# ecg_leaddetection_module_v2_0_1_jan2024.net
KiCad netlist of a schematic drawn in EAGLE
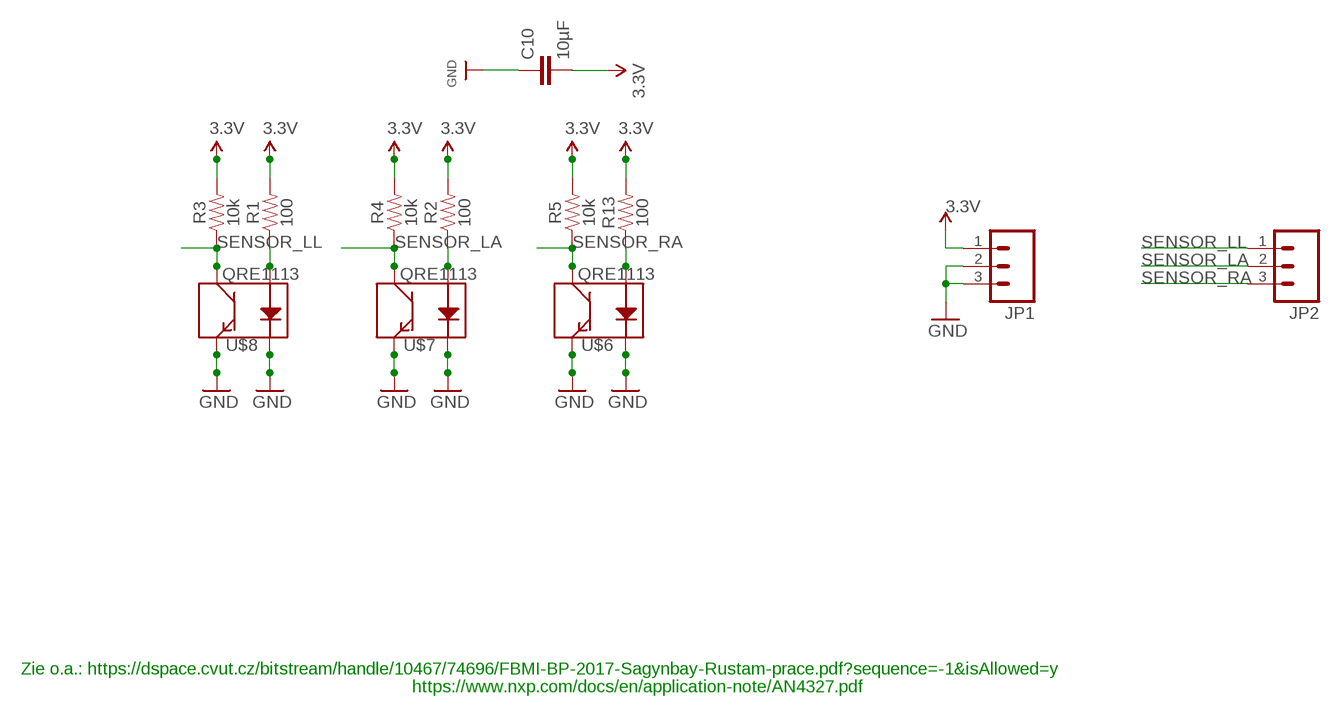
[diagram p0: schematic, sheet 1]

(export (version "E")
  (design (tool "Eeschema 10.0.6"))
  (components
    (comp (ref "C10")
      (value "10µF")
      (footprint "eagle-import:C0805")
      (libsource (lib "eagle-import") (part "C-EUC0805"))
    )
    (comp (ref "JP1")
      (value "M03PTH")
      (footprint "eagle-import:1X03")
      (libsource (lib "eagle-import") (part "M03PTH"))
    )
    (comp (ref "JP2")
      (value "M03PTH")
      (footprint "eagle-import:1X03")
      (libsource (lib "eagle-import") (part "M03PTH"))
    )
    (comp (ref "R1")
      (value "100")
      (footprint "eagle-import:0603")
      (libsource (lib "eagle-import") (part "100OHM-0603-1/4W-5%"))
    )
    (comp (ref "R2")
      (value "100")
      (footprint "eagle-import:0603")
      (libsource (lib "eagle-import") (part "100OHM-0603-1/4W-5%"))
    )
    (comp (ref "R3")
      (value "10k")
      (footprint "eagle-import:0603")
      (libsource (lib "eagle-import") (part "10KOHM-0603-1/10W-1%"))
    )
    (comp (ref "R4")
      (value "10k")
      (footprint "eagle-import:0603")
      (libsource (lib "eagle-import") (part "10KOHM-0603-1/10W-1%"))
    )
    (comp (ref "R5")
      (value "10k")
      (footprint "eagle-import:0603")
      (libsource (lib "eagle-import") (part "10KOHM-0603-1/10W-1%"))
    )
    (comp (ref "R13")
      (value "100")
      (footprint "eagle-import:0603")
      (libsource (lib "eagle-import") (part "100OHM-0603-1/4W-5%"))
    )
    (comp (ref "U$6")
      (value "QRE1113")
      (footprint "eagle-import:QRE1113")
      (libsource (lib "eagle-import") (part "QRE1113"))
    )
    (comp (ref "U$7")
      (value "QRE1113")
      (footprint "eagle-import:QRE1113")
      (libsource (lib "eagle-import") (part "QRE1113"))
    )
    (comp (ref "U$8")
      (value "QRE1113")
      (footprint "eagle-import:QRE1113")
      (libsource (lib "eagle-import") (part "QRE1113"))
    )
  )
  (nets
    (net (code "1") (name "/SENSOR_LA") (class "Default")
      (node (ref "JP2") (pin "2") (pinfunction "2_2") (pintype "passive"))
      (node (ref "R4") (pin "1") (pinfunction "1_1") (pintype "passive"))
      (node (ref "U$7") (pin "3") (pinfunction "C_3") (pintype "bidirectional"))
    )
    (net (code "2") (name "/SENSOR_LL") (class "Default")
      (node (ref "JP2") (pin "1") (pinfunction "1_1") (pintype "passive"))
      (node (ref "R3") (pin "1") (pinfunction "1_1") (pintype "passive"))
      (node (ref "U$8") (pin "3") (pinfunction "C_3") (pintype "bidirectional"))
    )
    (net (code "3") (name "/SENSOR_RA") (class "Default")
      (node (ref "JP2") (pin "3") (pinfunction "3_3") (pintype "passive"))
      (node (ref "R5") (pin "1") (pinfunction "1_1") (pintype "passive"))
      (node (ref "U$6") (pin "3") (pinfunction "C_3") (pintype "bidirectional"))
    )
    (net (code "4") (name "3.3V") (class "Default")
      (node (ref "C10") (pin "2") (pinfunction "2_2") (pintype "passive"))
      (node (ref "JP1") (pin "1") (pinfunction "1_1") (pintype "passive"))
      (node (ref "R1") (pin "2") (pinfunction "2_2") (pintype "passive"))
      (node (ref "R13") (pin "2") (pinfunction "2_2") (pintype "passive"))
      (node (ref "R2") (pin "2") (pinfunction "2_2") (pintype "passive"))
      (node (ref "R3") (pin "2") (pinfunction "2_2") (pintype "passive"))
      (node (ref "R4") (pin "2") (pinfunction "2_2") (pintype "passive"))
      (node (ref "R5") (pin "2") (pinfunction "2_2") (pintype "passive"))
    )
    (net (code "5") (name "GND") (class "Default")
      (node (ref "C10") (pin "1") (pinfunction "1_1") (pintype "passive"))
      (node (ref "JP1") (pin "2") (pinfunction "2_2") (pintype "passive"))
      (node (ref "JP1") (pin "3") (pinfunction "3_3") (pintype "passive"))
      (node (ref "U$6") (pin "2") (pinfunction "K_2") (pintype "bidirectional"))
      (node (ref "U$6") (pin "4") (pinfunction "E_4") (pintype "bidirectional"))
      (node (ref "U$7") (pin "2") (pinfunction "K_2") (pintype "bidirectional"))
      (node (ref "U$7") (pin "4") (pinfunction "E_4") (pintype "bidirectional"))
      (node (ref "U$8") (pin "2") (pinfunction "K_2") (pintype "bidirectional"))
      (node (ref "U$8") (pin "4") (pinfunction "E_4") (pintype "bidirectional"))
    )
    (net (code "6") (name "Net-(U$6-A)") (class "Default")
      (node (ref "R13") (pin "1") (pinfunction "1_1") (pintype "passive"))
      (node (ref "U$6") (pin "1") (pinfunction "A_1") (pintype "bidirectional"))
    )
    (net (code "7") (name "Net-(U$7-A)") (class "Default")
      (node (ref "R2") (pin "1") (pinfunction "1_1") (pintype "passive"))
      (node (ref "U$7") (pin "1") (pinfunction "A_1") (pintype "bidirectional"))
    )
    (net (code "8") (name "Net-(U$8-A)") (class "Default")
      (node (ref "R1") (pin "1") (pinfunction "1_1") (pintype "passive"))
      (node (ref "U$8") (pin "1") (pinfunction "A_1") (pintype "bidirectional"))
    )
  )
)
